# LightBox1.net
KiCad netlist of a schematic drawn in EAGLE
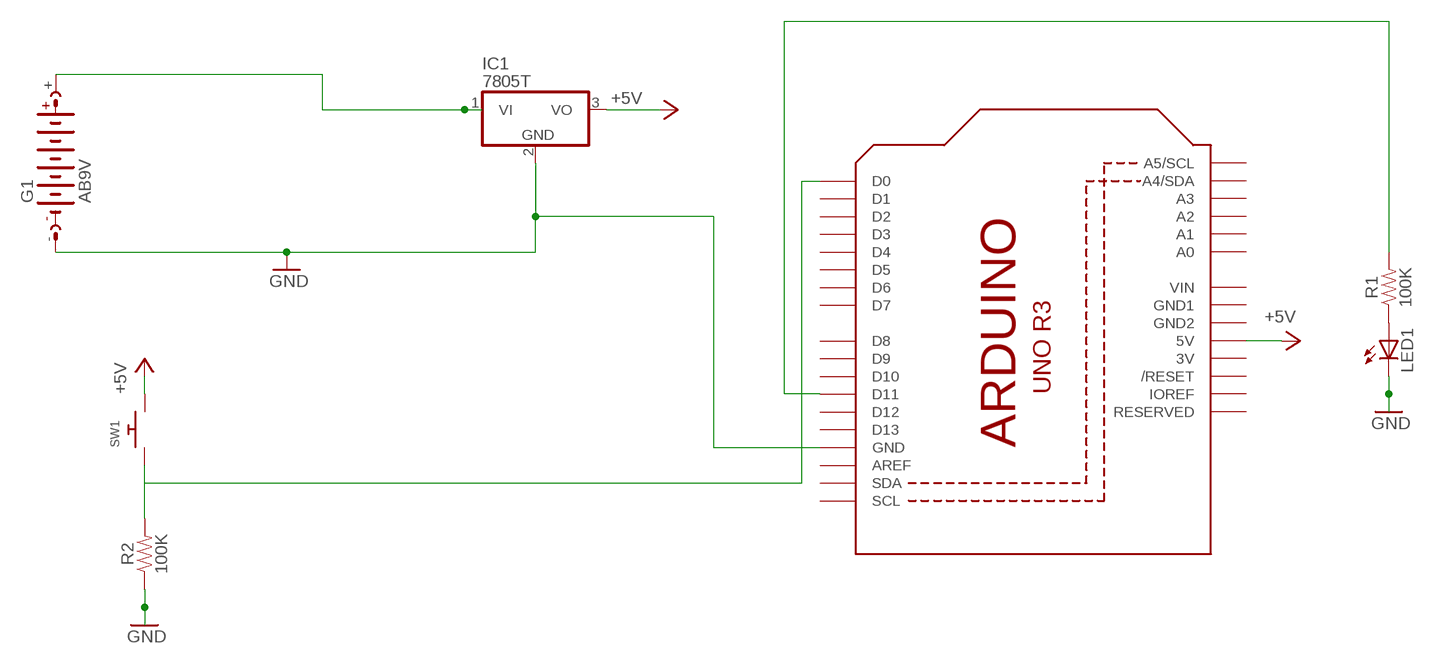
[diagram p0: schematic, sheet 1]

(export (version "E")
  (design (tool "Eeschema 10.0.6"))
  (components
    (comp (ref "G1")
      (value "AB9V")
      (footprint "eagle-import:AB9V")
      (libsource (lib "eagle-import") (part "AB9V"))
    )
    (comp (ref "IC1")
      (value "7805T")
      (footprint "eagle-import:TO220H")
      (libsource (lib "eagle-import") (part "78T05"))
    )
    (comp (ref "LED1")
      (value "LED3MM")
      (footprint "eagle-import:LED3MM")
      (libsource (lib "eagle-import") (part "LED3MM"))
    )
    (comp (ref "R1")
      (value "100K")
      (footprint "eagle-import:0402")
      (libsource (lib "eagle-import") (part "100KOHM-0402-1/16W-1%"))
    )
    (comp (ref "R2")
      (value "100K")
      (footprint "eagle-import:0402")
      (libsource (lib "eagle-import") (part "100KOHM-0402-1/16W-1%"))
    )
    (comp (ref "SW1")
      (value "SWITCH_PUSHBUTTONSOFTTOUCHSMD_SJ")
      (footprint "eagle-import:PUSHBUTTON_SMD_SJ")
      (libsource (lib "eagle-import") (part "SWITCH_PUSHBUTTONSOFTTOUCHSMD_SJ"))
    )
    (comp (ref "U1")
      (value "ARDUINOR3-DIMENSION")
      (footprint "eagle-import:ARDUINOR3")
      (libsource (lib "eagle-import") (part "ARDUINOR3-DIMENSION"))
    )
  )
  (nets
    (net (code "1") (name "+5V") (class "Default")
      (node (ref "IC1") (pin "3") (pinfunction "VO_3") (pintype "passive"))
      (node (ref "SW1") (pin "P$2") (pinfunction "P$2_P$2") (pintype "passive"))
      (node (ref "U1") (pin "5V") (pinfunction "5V_5V") (pintype "power_in"))
    )
    (net (code "2") (name "/3V") (class "Default")
      (node (ref "U1") (pin "3V") (pinfunction "3V_3V") (pintype "power_in"))
    )
    (net (code "3") (name "/GND1") (class "Default")
      (node (ref "U1") (pin "GND1") (pinfunction "GND1_GND1") (pintype "power_in"))
    )
    (net (code "4") (name "/GND2") (class "Default")
      (node (ref "U1") (pin "GND2") (pinfunction "GND2_GND2") (pintype "power_in"))
    )
    (net (code "5") (name "/VIN") (class "Default")
      (node (ref "U1") (pin "VIN") (pinfunction "VIN_VIN") (pintype "power_in"))
    )
    (net (code "6") (name "GND") (class "Default")
      (node (ref "G1") (pin "-") (pinfunction "-_-") (pintype "passive"))
      (node (ref "IC1") (pin "2") (pinfunction "GND_2") (pintype "passive"))
      (node (ref "LED1") (pin "K") (pinfunction "C_K") (pintype "passive"))
      (node (ref "R2") (pin "1") (pinfunction "1_1") (pintype "passive"))
      (node (ref "U1") (pin "GND") (pinfunction "GND_GND") (pintype "power_in"))
    )
    (net (code "7") (name "Net-(IC1-VI)") (class "Default")
      (node (ref "G1") (pin "+") (pinfunction "+_+") (pintype "passive"))
      (node (ref "IC1") (pin "1") (pinfunction "VI_1") (pintype "input"))
    )
    (net (code "8") (name "Net-(LED1-PadA)") (class "Default")
      (node (ref "LED1") (pin "A") (pinfunction "A_A") (pintype "passive"))
      (node (ref "R1") (pin "1") (pinfunction "1_1") (pintype "passive"))
    )
    (net (code "9") (name "Net-(R1-Pad2)") (class "Default")
      (node (ref "R1") (pin "2") (pinfunction "2_2") (pintype "passive"))
      (node (ref "U1") (pin "D11") (pinfunction "D11_D11") (pintype "bidirectional"))
    )
    (net (code "10") (name "Net-(R2-Pad2)") (class "Default")
      (node (ref "R2") (pin "2") (pinfunction "2_2") (pintype "passive"))
      (node (ref "SW1") (pin "P$1") (pinfunction "P$1_P$1") (pintype "passive"))
      (node (ref "U1") (pin "D0") (pinfunction "D0_D0") (pintype "bidirectional"))
    )
    (net (code "11") (name "unconnected-(U1-A4{slash}SDA-PadA4)") (class "Default")
      (node (ref "U1") (pin "A4") (pinfunction "A4/SDA_A4") (pintype "bidirectional"))
    )
    (net (code "12") (name "unconnected-(U1-A5{slash}SCL-PadA5)") (class "Default")
      (node (ref "U1") (pin "A5") (pinfunction "A5/SCL_A5") (pintype "bidirectional"))
    )
    (net (code "13") (name "unconnected-(U1-PadA0)") (class "Default")
      (node (ref "U1") (pin "A0") (pinfunction "A0_A0") (pintype "bidirectional"))
    )
    (net (code "14") (name "unconnected-(U1-PadA1)") (class "Default")
      (node (ref "U1") (pin "A1") (pinfunction "A1_A1") (pintype "bidirectional"))
    )
    (net (code "15") (name "unconnected-(U1-PadA2)") (class "Default")
      (node (ref "U1") (pin "A2") (pinfunction "A2_A2") (pintype "bidirectional"))
    )
    (net (code "16") (name "unconnected-(U1-PadA3)") (class "Default")
      (node (ref "U1") (pin "A3") (pinfunction "A3_A3") (pintype "bidirectional"))
    )
    (net (code "17") (name "unconnected-(U1-PadAREF)") (class "Default")
      (node (ref "U1") (pin "AREF") (pinfunction "AREF_AREF") (pintype "bidirectional"))
    )
    (net (code "18") (name "unconnected-(U1-PadD1)") (class "Default")
      (node (ref "U1") (pin "D1") (pinfunction "D1_D1") (pintype "bidirectional"))
    )
    (net (code "19") (name "unconnected-(U1-PadD2)") (class "Default")
      (node (ref "U1") (pin "D2") (pinfunction "D2_D2") (pintype "bidirectional"))
    )
    (net (code "20") (name "unconnected-(U1-PadD3)") (class "Default")
      (node (ref "U1") (pin "D3") (pinfunction "D3_D3") (pintype "bidirectional"))
    )
    (net (code "21") (name "unconnected-(U1-PadD4)") (class "Default")
      (node (ref "U1") (pin "D4") (pinfunction "D4_D4") (pintype "bidirectional"))
    )
    (net (code "22") (name "unconnected-(U1-PadD5)") (class "Default")
      (node (ref "U1") (pin "D5") (pinfunction "D5_D5") (pintype "bidirectional"))
    )
    (net (code "23") (name "unconnected-(U1-PadD6)") (class "Default")
      (node (ref "U1") (pin "D6") (pinfunction "D6_D6") (pintype "bidirectional"))
    )
    (net (code "24") (name "unconnected-(U1-PadD7)") (class "Default")
      (node (ref "U1") (pin "D7") (pinfunction "D7_D7") (pintype "bidirectional"))
    )
    (net (code "25") (name "unconnected-(U1-PadD8)") (class "Default")
      (node (ref "U1") (pin "D8") (pinfunction "D8_D8") (pintype "bidirectional"))
    )
    (net (code "26") (name "unconnected-(U1-PadD9)") (class "Default")
      (node (ref "U1") (pin "D9") (pinfunction "D9_D9") (pintype "bidirectional"))
    )
    (net (code "27") (name "unconnected-(U1-PadD10)") (class "Default")
      (node (ref "U1") (pin "D10") (pinfunction "D10_D10") (pintype "bidirectional"))
    )
    (net (code "28") (name "unconnected-(U1-PadD12)") (class "Default")
      (node (ref "U1") (pin "D12") (pinfunction "D12_D12") (pintype "bidirectional"))
    )
    (net (code "29") (name "unconnected-(U1-PadD13)") (class "Default")
      (node (ref "U1") (pin "D13") (pinfunction "D13_D13") (pintype "bidirectional"))
    )
    (net (code "30") (name "unconnected-(U1-PadIOREF)") (class "Default")
      (node (ref "U1") (pin "IOREF") (pinfunction "IOREF_IOREF") (pintype "output"))
    )
    (net (code "31") (name "unconnected-(U1-PadRESERVED)") (class "Default")
      (node (ref "U1") (pin "RESERVED") (pinfunction "RESERVED_RESERVED") (pintype "no_connect"))
    )
    (net (code "32") (name "unconnected-(U1-PadSCL)") (class "Default")
      (node (ref "U1") (pin "SCL") (pinfunction "SCL_SCL") (pintype "bidirectional"))
    )
    (net (code "33") (name "unconnected-(U1-PadSDA)") (class "Default")
      (node (ref "U1") (pin "SDA") (pinfunction "SDA_SDA") (pintype "bidirectional"))
    )
    (net (code "34") (name "unconnected-(U1-{slash}RESET-PadRESET)") (class "Default")
      (node (ref "U1") (pin "RESET") (pinfunction "/RESET_RESET") (pintype "bidirectional"))
    )
  )
)
